# 64_Electrode_Wafer.net
KiCad netlist of a schematic drawn in Altium Designer
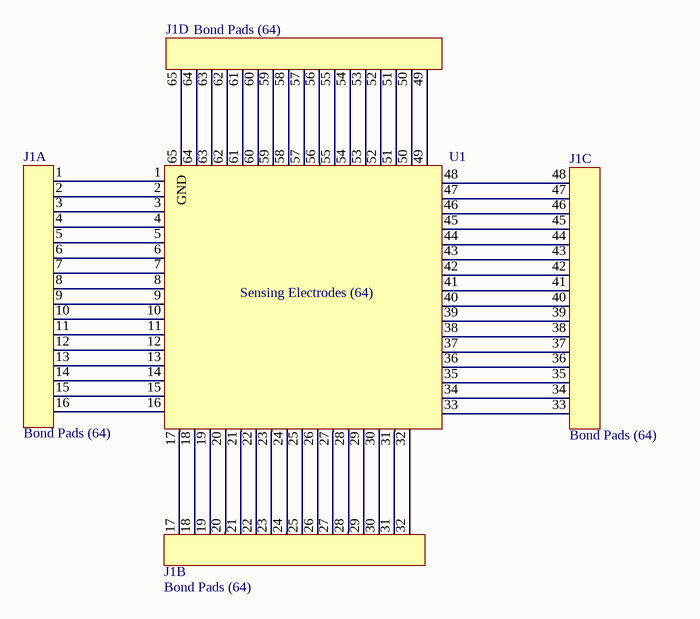
[diagram p0: 64 Electrode Wafer.SchDoc]

(export (version "E")
  (design (tool "Eeschema 10.0.6"))
  (components
    (comp (ref "J1")
      (value "Bond Pads (64)")
      (footprint "Bond Pads (64)")
      (description "64 bond pads for 64 channel wafer")
      (libsource (lib "Celestial Library Database") (part "Bond Pads (64)"))
    )
    (comp (ref "U1")
      (value "Sensing Electrodes (64)")
      (footprint "Sensing Area (64)")
      (description "64 Electrodes covering a 2 mm by 2 mm sensing area")
      (fields (field (name "PART NUMBER") "64 Electrode Sensing Area"))
      (libsource (lib "Celestial Library Database") (part "Sensing Electrodes (64)"))
    )
  )
  (nets
    (net (code "1") (name "Net-(J1-Pad1)") (class "Default")
      (node (ref "J1") (pin "1") (pintype "input"))
      (node (ref "U1") (pin "1") (pintype "input"))
    )
    (net (code "2") (name "Net-(J1-Pad2)") (class "Default")
      (node (ref "J1") (pin "2") (pintype "input"))
      (node (ref "U1") (pin "2") (pintype "input"))
    )
    (net (code "3") (name "Net-(J1-Pad3)") (class "Default")
      (node (ref "J1") (pin "3") (pintype "input"))
      (node (ref "U1") (pin "3") (pintype "input"))
    )
    (net (code "4") (name "Net-(J1-Pad4)") (class "Default")
      (node (ref "J1") (pin "4") (pintype "input"))
      (node (ref "U1") (pin "4") (pintype "input"))
    )
    (net (code "5") (name "Net-(J1-Pad5)") (class "Default")
      (node (ref "J1") (pin "5") (pintype "input"))
      (node (ref "U1") (pin "5") (pintype "input"))
    )
    (net (code "6") (name "Net-(J1-Pad6)") (class "Default")
      (node (ref "J1") (pin "6") (pintype "input"))
      (node (ref "U1") (pin "6") (pintype "input"))
    )
    (net (code "7") (name "Net-(J1-Pad7)") (class "Default")
      (node (ref "J1") (pin "7") (pintype "input"))
      (node (ref "U1") (pin "7") (pintype "input"))
    )
    (net (code "8") (name "Net-(J1-Pad8)") (class "Default")
      (node (ref "J1") (pin "8") (pintype "input"))
      (node (ref "U1") (pin "8") (pintype "input"))
    )
    (net (code "9") (name "Net-(J1-Pad9)") (class "Default")
      (node (ref "J1") (pin "9") (pintype "input"))
      (node (ref "U1") (pin "9") (pintype "input"))
    )
    (net (code "10") (name "Net-(J1-Pad10)") (class "Default")
      (node (ref "J1") (pin "10") (pintype "input"))
      (node (ref "U1") (pin "10") (pintype "input"))
    )
    (net (code "11") (name "Net-(J1-Pad11)") (class "Default")
      (node (ref "J1") (pin "11") (pintype "input"))
      (node (ref "U1") (pin "11") (pintype "input"))
    )
    (net (code "12") (name "Net-(J1-Pad12)") (class "Default")
      (node (ref "J1") (pin "12") (pintype "input"))
      (node (ref "U1") (pin "12") (pintype "input"))
    )
    (net (code "13") (name "Net-(J1-Pad13)") (class "Default")
      (node (ref "J1") (pin "13") (pintype "input"))
      (node (ref "U1") (pin "13") (pintype "input"))
    )
    (net (code "14") (name "Net-(J1-Pad14)") (class "Default")
      (node (ref "J1") (pin "14") (pintype "input"))
      (node (ref "U1") (pin "14") (pintype "input"))
    )
    (net (code "15") (name "Net-(J1-Pad15)") (class "Default")
      (node (ref "J1") (pin "15") (pintype "input"))
      (node (ref "U1") (pin "15") (pintype "input"))
    )
    (net (code "16") (name "Net-(J1-Pad16)") (class "Default")
      (node (ref "J1") (pin "16") (pintype "input"))
      (node (ref "U1") (pin "16") (pintype "input"))
    )
    (net (code "17") (name "Net-(J1-Pad17)") (class "Default")
      (node (ref "J1") (pin "17") (pintype "input"))
      (node (ref "U1") (pin "17") (pintype "input"))
    )
    (net (code "18") (name "Net-(J1-Pad18)") (class "Default")
      (node (ref "J1") (pin "18") (pintype "input"))
      (node (ref "U1") (pin "18") (pintype "input"))
    )
    (net (code "19") (name "Net-(J1-Pad19)") (class "Default")
      (node (ref "J1") (pin "19") (pintype "input"))
      (node (ref "U1") (pin "19") (pintype "input"))
    )
    (net (code "20") (name "Net-(J1-Pad20)") (class "Default")
      (node (ref "J1") (pin "20") (pintype "input"))
      (node (ref "U1") (pin "20") (pintype "input"))
    )
    (net (code "21") (name "Net-(J1-Pad21)") (class "Default")
      (node (ref "J1") (pin "21") (pintype "input"))
      (node (ref "U1") (pin "21") (pintype "input"))
    )
    (net (code "22") (name "Net-(J1-Pad22)") (class "Default")
      (node (ref "J1") (pin "22") (pintype "input"))
      (node (ref "U1") (pin "22") (pintype "input"))
    )
    (net (code "23") (name "Net-(J1-Pad23)") (class "Default")
      (node (ref "J1") (pin "23") (pintype "input"))
      (node (ref "U1") (pin "23") (pintype "input"))
    )
    (net (code "24") (name "Net-(J1-Pad24)") (class "Default")
      (node (ref "J1") (pin "24") (pintype "input"))
      (node (ref "U1") (pin "24") (pintype "input"))
    )
    (net (code "25") (name "Net-(J1-Pad25)") (class "Default")
      (node (ref "J1") (pin "25") (pintype "input"))
      (node (ref "U1") (pin "25") (pintype "input"))
    )
    (net (code "26") (name "Net-(J1-Pad26)") (class "Default")
      (node (ref "J1") (pin "26") (pintype "input"))
      (node (ref "U1") (pin "26") (pintype "input"))
    )
    (net (code "27") (name "Net-(J1-Pad27)") (class "Default")
      (node (ref "J1") (pin "27") (pintype "input"))
      (node (ref "U1") (pin "27") (pintype "input"))
    )
    (net (code "28") (name "Net-(J1-Pad28)") (class "Default")
      (node (ref "J1") (pin "28") (pintype "input"))
      (node (ref "U1") (pin "28") (pintype "input"))
    )
    (net (code "29") (name "Net-(J1-Pad29)") (class "Default")
      (node (ref "J1") (pin "29") (pintype "input"))
      (node (ref "U1") (pin "29") (pintype "input"))
    )
    (net (code "30") (name "Net-(J1-Pad30)") (class "Default")
      (node (ref "J1") (pin "30") (pintype "input"))
      (node (ref "U1") (pin "30") (pintype "input"))
    )
    (net (code "31") (name "Net-(J1-Pad31)") (class "Default")
      (node (ref "J1") (pin "31") (pintype "input"))
      (node (ref "U1") (pin "31") (pintype "input"))
    )
    (net (code "32") (name "Net-(J1-Pad32)") (class "Default")
      (node (ref "J1") (pin "32") (pintype "input"))
      (node (ref "U1") (pin "32") (pintype "input"))
    )
    (net (code "33") (name "Net-(J1-Pad33)") (class "Default")
      (node (ref "J1") (pin "33") (pintype "input"))
      (node (ref "U1") (pin "33") (pintype "input"))
    )
    (net (code "34") (name "Net-(J1-Pad34)") (class "Default")
      (node (ref "J1") (pin "34") (pintype "input"))
      (node (ref "U1") (pin "34") (pintype "input"))
    )
    (net (code "35") (name "Net-(J1-Pad35)") (class "Default")
      (node (ref "J1") (pin "35") (pintype "input"))
      (node (ref "U1") (pin "35") (pintype "input"))
    )
    (net (code "36") (name "Net-(J1-Pad36)") (class "Default")
      (node (ref "J1") (pin "36") (pintype "input"))
      (node (ref "U1") (pin "36") (pintype "input"))
    )
    (net (code "37") (name "Net-(J1-Pad37)") (class "Default")
      (node (ref "J1") (pin "37") (pintype "input"))
      (node (ref "U1") (pin "37") (pintype "input"))
    )
    (net (code "38") (name "Net-(J1-Pad38)") (class "Default")
      (node (ref "J1") (pin "38") (pintype "input"))
      (node (ref "U1") (pin "38") (pintype "input"))
    )
    (net (code "39") (name "Net-(J1-Pad39)") (class "Default")
      (node (ref "J1") (pin "39") (pintype "input"))
      (node (ref "U1") (pin "39") (pintype "input"))
    )
    (net (code "40") (name "Net-(J1-Pad40)") (class "Default")
      (node (ref "J1") (pin "40") (pintype "input"))
      (node (ref "U1") (pin "40") (pintype "input"))
    )
    (net (code "41") (name "Net-(J1-Pad41)") (class "Default")
      (node (ref "J1") (pin "41") (pintype "input"))
      (node (ref "U1") (pin "41") (pintype "input"))
    )
    (net (code "42") (name "Net-(J1-Pad42)") (class "Default")
      (node (ref "J1") (pin "42") (pintype "input"))
      (node (ref "U1") (pin "42") (pintype "input"))
    )
    (net (code "43") (name "Net-(J1-Pad43)") (class "Default")
      (node (ref "J1") (pin "43") (pintype "input"))
      (node (ref "U1") (pin "43") (pintype "input"))
    )
    (net (code "44") (name "Net-(J1-Pad44)") (class "Default")
      (node (ref "J1") (pin "44") (pintype "input"))
      (node (ref "U1") (pin "44") (pintype "input"))
    )
    (net (code "45") (name "Net-(J1-Pad45)") (class "Default")
      (node (ref "J1") (pin "45") (pintype "input"))
      (node (ref "U1") (pin "45") (pintype "input"))
    )
    (net (code "46") (name "Net-(J1-Pad46)") (class "Default")
      (node (ref "J1") (pin "46") (pintype "input"))
      (node (ref "U1") (pin "46") (pintype "input"))
    )
    (net (code "47") (name "Net-(J1-Pad47)") (class "Default")
      (node (ref "J1") (pin "47") (pintype "input"))
      (node (ref "U1") (pin "47") (pintype "input"))
    )
    (net (code "48") (name "Net-(J1-Pad48)") (class "Default")
      (node (ref "J1") (pin "48") (pintype "input"))
      (node (ref "U1") (pin "48") (pintype "input"))
    )
    (net (code "49") (name "Net-(J1-Pad49)") (class "Default")
      (node (ref "J1") (pin "49") (pintype "input"))
      (node (ref "U1") (pin "49") (pintype "input"))
    )
    (net (code "50") (name "Net-(J1-Pad50)") (class "Default")
      (node (ref "J1") (pin "50") (pintype "input"))
      (node (ref "U1") (pin "50") (pintype "input"))
    )
    (net (code "51") (name "Net-(J1-Pad51)") (class "Default")
      (node (ref "J1") (pin "51") (pintype "input"))
      (node (ref "U1") (pin "51") (pintype "input"))
    )
    (net (code "52") (name "Net-(J1-Pad52)") (class "Default")
      (node (ref "J1") (pin "52") (pintype "input"))
      (node (ref "U1") (pin "52") (pintype "input"))
    )
    (net (code "53") (name "Net-(J1-Pad53)") (class "Default")
      (node (ref "J1") (pin "53") (pintype "input"))
      (node (ref "U1") (pin "53") (pintype "input"))
    )
    (net (code "54") (name "Net-(J1-Pad54)") (class "Default")
      (node (ref "J1") (pin "54") (pintype "input"))
      (node (ref "U1") (pin "54") (pintype "input"))
    )
    (net (code "55") (name "Net-(J1-Pad55)") (class "Default")
      (node (ref "J1") (pin "55") (pintype "input"))
      (node (ref "U1") (pin "55") (pintype "input"))
    )
    (net (code "56") (name "Net-(J1-Pad56)") (class "Default")
      (node (ref "J1") (pin "56") (pintype "input"))
      (node (ref "U1") (pin "56") (pintype "input"))
    )
    (net (code "57") (name "Net-(J1-Pad57)") (class "Default")
      (node (ref "J1") (pin "57") (pintype "input"))
      (node (ref "U1") (pin "57") (pintype "input"))
    )
    (net (code "58") (name "Net-(J1-Pad58)") (class "Default")
      (node (ref "J1") (pin "58") (pintype "input"))
      (node (ref "U1") (pin "58") (pintype "input"))
    )
    (net (code "59") (name "Net-(J1-Pad59)") (class "Default")
      (node (ref "J1") (pin "59") (pintype "input"))
      (node (ref "U1") (pin "59") (pintype "input"))
    )
    (net (code "60") (name "Net-(J1-Pad60)") (class "Default")
      (node (ref "J1") (pin "60") (pintype "input"))
      (node (ref "U1") (pin "60") (pintype "input"))
    )
    (net (code "61") (name "Net-(J1-Pad61)") (class "Default")
      (node (ref "J1") (pin "61") (pintype "input"))
      (node (ref "U1") (pin "61") (pintype "input"))
    )
    (net (code "62") (name "Net-(J1-Pad62)") (class "Default")
      (node (ref "J1") (pin "62") (pintype "input"))
      (node (ref "U1") (pin "62") (pintype "input"))
    )
    (net (code "63") (name "Net-(J1-Pad63)") (class "Default")
      (node (ref "J1") (pin "63") (pintype "input"))
      (node (ref "U1") (pin "63") (pintype "input"))
    )
    (net (code "64") (name "Net-(J1-Pad64)") (class "Default")
      (node (ref "J1") (pin "64") (pintype "input"))
      (node (ref "U1") (pin "64") (pintype "input"))
    )
    (net (code "65") (name "Net-(U1-GND)") (class "Default")
      (node (ref "J1") (pin "65") (pintype "input"))
      (node (ref "U1") (pin "65") (pinfunction "GND_65") (pintype "input"))
    )
  )
)
